# 1-Schematic_IoT_Board.net
KiCad netlist of a schematic drawn in EasyEDA
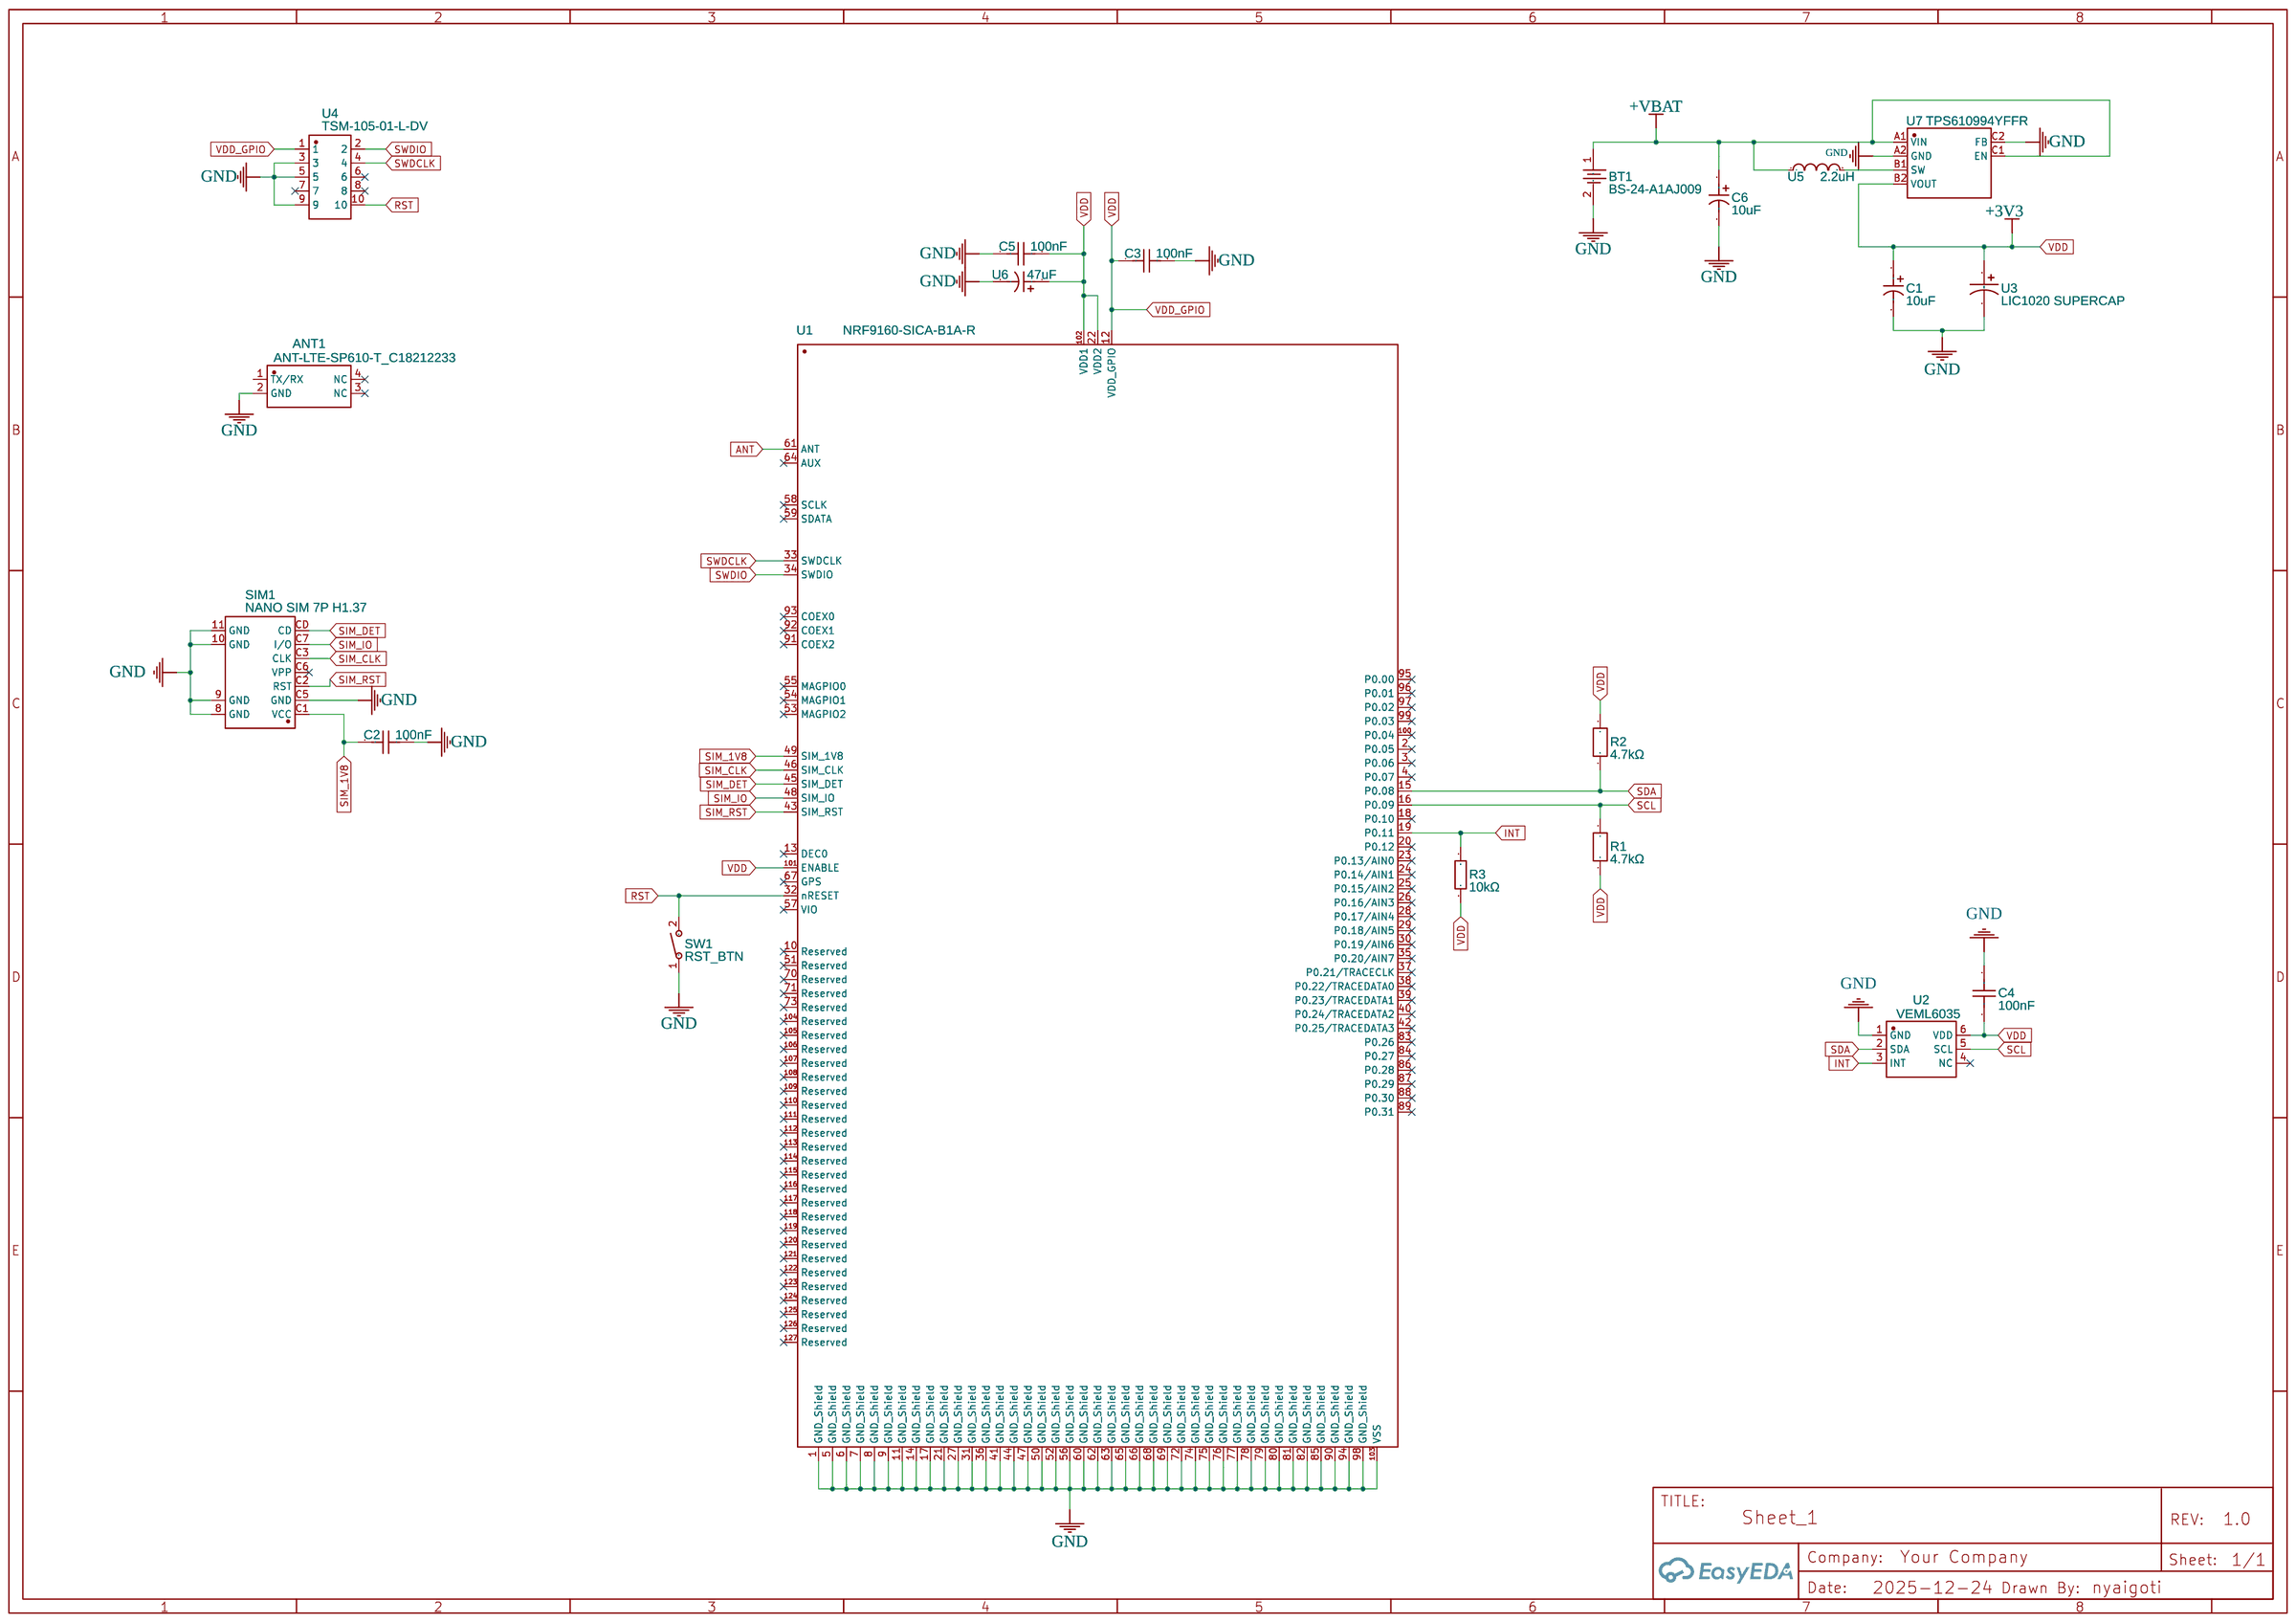
[diagram p0: schematic sheet]

(export (version "E")
  (design (tool "Eeschema 10.0.6"))
  (components
    (comp (ref "ANT1")
      (value "ANT-LTE-SP610-T_C18212233")
      (fields
        (field (name "Manufacturer Part") "ANT-LTE-SP610-T")
        (field (name "Manufacturer") "TE Connectivity(泰科电子)")
      )
      (libsource (lib "") (part "ANT-LTE-SP610-T_C18212233"))
    )
    (comp (ref "BT1")
      (value "BS-24-A1AJ009")
      (fields (field (name "Manufacturer") "MYOUNG(美阳)"))
      (libsource (lib "") (part "BS-24-A1AJ009"))
    )
    (comp (ref "C1")
      (value "10uF")
      (fields
        (field (name "Manufacturer Part") "293D106X9016B2TE3")
        (field (name "Manufacturer") "VISHAY(威世)")
      )
      (libsource (lib "") (part "293D106X9016B2TE3"))
    )
    (comp (ref "C2")
      (value "100nF")
      (fields
        (field (name "Manufacturer Part") "FCC0603B104K500CT")
        (field (name "Manufacturer") "FOJAN(富捷)")
      )
      (libsource (lib "") (part "FCC0603B104K500CT"))
    )
    (comp (ref "C3")
      (value "100nF")
      (fields
        (field (name "Manufacturer Part") "FCC0603B104K500CT")
        (field (name "Manufacturer") "FOJAN(富捷)")
      )
      (libsource (lib "") (part "FCC0603B104K500CT"))
    )
    (comp (ref "C4")
      (value "100nF")
      (fields
        (field (name "Manufacturer Part") "FCC0603B104K500CT")
        (field (name "Manufacturer") "FOJAN(富捷)")
      )
      (libsource (lib "") (part "FCC0603B104K500CT_1"))
    )
    (comp (ref "C5")
      (value "100nF")
      (fields
        (field (name "Manufacturer Part") "FCC0603B104K500CT")
        (field (name "Manufacturer") "FOJAN(富捷)")
      )
      (libsource (lib "") (part "FCC0603B104K500CT"))
    )
    (comp (ref "C6")
      (value "10uF")
      (fields
        (field (name "Manufacturer Part") "293D106X9016B2TE3")
        (field (name "Manufacturer") "VISHAY(威世)")
      )
      (libsource (lib "") (part "293D106X9016B2TE3"))
    )
    (comp (ref "R1")
      (value "4.7kΩ")
      (fields
        (field (name "Manufacturer Part") "CR0603F4K70P05Z")
        (field (name "Manufacturer") "EVER OHMS(天二科技)")
      )
      (libsource (lib "") (part "CR0603F4K70P05Z"))
    )
    (comp (ref "R2")
      (value "4.7kΩ")
      (fields
        (field (name "Manufacturer Part") "CR0603F4K70P05Z")
        (field (name "Manufacturer") "EVER OHMS(天二科技)")
      )
      (libsource (lib "") (part "CR0603F4K70P05Z_1"))
    )
    (comp (ref "R3")
      (value "10kΩ")
      (fields
        (field (name "Manufacturer Part") "TR0603B10K0P0525Z")
        (field (name "Manufacturer") "EVER OHMS(天二科技)")
      )
      (libsource (lib "") (part "TR0603B10KP05250.1W"))
    )
    (comp (ref "SIM1")
      (value "NANO SIM 7P H1.37")
      (fields (field (name "Manufacturer") "SHOU HAN(首韩)"))
      (libsource (lib "") (part "NANO SIM 7P H1.37"))
    )
    (comp (ref "SW1")
      (value "RST_BTN")
      (fields
        (field (name "Manufacturer Part") "HX 3x4x2-2P-1.6N TACTILE SWITCH")
        (field (name "Manufacturer") "hanxia(韩下)")
      )
      (libsource (lib "") (part "HX 3X4X2-2P-1.6N TACTILE SWITCH"))
    )
    (comp (ref "U1")
      (value "NRF9160-SICA-B1A-R")
      (fields (field (name "Manufacturer") "NORDIC"))
      (libsource (lib "") (part "NRF9160-SICA-B1A-R"))
    )
    (comp (ref "U2")
      (value "VEML6035")
      (fields (field (name "Manufacturer") "VISHAY(威世)"))
      (libsource (lib "") (part "VEML6035"))
    )
    (comp (ref "U3")
      (value "LIC1020 SUPERCAP")
      (fields
        (field (name "Manufacturer Part") "LIC1020N3R8C080")
        (field (name "Manufacturer") "KNSCHA(科尼盛)")
      )
      (libsource (lib "") (part "LIC1020N3R8C080"))
    )
    (comp (ref "U4")
      (value "TSM-105-01-L-DV")
      (fields (field (name "Manufacturer") "SAMTEC"))
      (libsource (lib "") (part "TSM-105-01-L-DV"))
    )
    (comp (ref "U5")
      (value "2.2uH")
      (fields (field (name "Manufacturer Part") "APH252010T2R2M") (field (name "Manufacturer") "APV(爱普微)"))
      (libsource (lib "") (part "APH252010T2R2M"))
    )
    (comp (ref "U6")
      (value "47uF")
      (fields
        (field (name "Manufacturer Part") "EMLA500ARA470MF80G")
        (field (name "Manufacturer") "NCC(日本贵弥功)")
      )
      (libsource (lib "") (part "EMLA500ARA470MF80G"))
    )
    (comp (ref "U7")
      (value "TPS610994YFFR")
      (fields (field (name "Manufacturer") "TI(德州仪器)"))
      (libsource (lib "") (part "TPS610994YFFR"))
    )
  )
  (nets
    (net (code "1") (name "+VBAT") (class "Default")
      (node (ref "BT1") (pin "1") (pinfunction "1_1") (pintype "input"))
      (node (ref "C6") (pin "1") (pinfunction "1_1") (pintype "input"))
      (node (ref "U5") (pin "1") (pinfunction "1_1") (pintype "unspecified"))
      (node (ref "U7") (pin "A1") (pinfunction "VIN_A1") (pintype "unspecified"))
      (node (ref "U7") (pin "C1") (pinfunction "EN_C1") (pintype "unspecified"))
    )
    (net (code "2") (name "ANT") (class "Default")
      (node (ref "U1") (pin "61") (pinfunction "ANT_61") (pintype "unspecified"))
    )
    (net (code "3") (name "GND") (class "Default")
      (node (ref "ANT1") (pin "2") (pinfunction "GND_2") (pintype "unspecified"))
      (node (ref "BT1") (pin "2") (pinfunction "2_2") (pintype "input"))
      (node (ref "C1") (pin "2") (pinfunction "2_2") (pintype "input"))
      (node (ref "C2") (pin "2") (pinfunction "2_2") (pintype "unspecified"))
      (node (ref "C3") (pin "2") (pinfunction "2_2") (pintype "unspecified"))
      (node (ref "C4") (pin "1") (pinfunction "1_1") (pintype "unspecified"))
      (node (ref "C5") (pin "1") (pinfunction "1_1") (pintype "unspecified"))
      (node (ref "C6") (pin "2") (pinfunction "2_2") (pintype "input"))
      (node (ref "SIM1") (pin "10") (pinfunction "GND_10") (pintype "unspecified"))
      (node (ref "SIM1") (pin "11") (pinfunction "GND_11") (pintype "unspecified"))
      (node (ref "SIM1") (pin "8") (pinfunction "GND_8") (pintype "unspecified"))
      (node (ref "SIM1") (pin "9") (pinfunction "GND_9") (pintype "unspecified"))
      (node (ref "SIM1") (pin "C5") (pinfunction "GND_C5") (pintype "unspecified"))
      (node (ref "SW1") (pin "1") (pinfunction "1_1") (pintype "unspecified"))
      (node (ref "U1") (pin "1") (pinfunction "GND_Shield_1") (pintype "unspecified"))
      (node (ref "U1") (pin "103") (pinfunction "VSS_103") (pintype "unspecified"))
      (node (ref "U1") (pin "11") (pinfunction "GND_Shield_11") (pintype "unspecified"))
      (node (ref "U1") (pin "14") (pinfunction "GND_Shield_14") (pintype "unspecified"))
      (node (ref "U1") (pin "17") (pinfunction "GND_Shield_17") (pintype "unspecified"))
      (node (ref "U1") (pin "21") (pinfunction "GND_Shield_21") (pintype "unspecified"))
      (node (ref "U1") (pin "27") (pinfunction "GND_Shield_27") (pintype "unspecified"))
      (node (ref "U1") (pin "31") (pinfunction "GND_Shield_31") (pintype "unspecified"))
      (node (ref "U1") (pin "36") (pinfunction "GND_Shield_36") (pintype "unspecified"))
      (node (ref "U1") (pin "41") (pinfunction "GND_Shield_41") (pintype "unspecified"))
      (node (ref "U1") (pin "44") (pinfunction "GND_Shield_44") (pintype "unspecified"))
      (node (ref "U1") (pin "47") (pinfunction "GND_Shield_47") (pintype "unspecified"))
      (node (ref "U1") (pin "5") (pinfunction "GND_Shield_5") (pintype "unspecified"))
      (node (ref "U1") (pin "50") (pinfunction "GND_Shield_50") (pintype "unspecified"))
      (node (ref "U1") (pin "52") (pinfunction "GND_Shield_52") (pintype "unspecified"))
      (node (ref "U1") (pin "56") (pinfunction "GND_Shield_56") (pintype "unspecified"))
      (node (ref "U1") (pin "6") (pinfunction "GND_Shield_6") (pintype "unspecified"))
      (node (ref "U1") (pin "60") (pinfunction "GND_Shield_60") (pintype "unspecified"))
      (node (ref "U1") (pin "62") (pinfunction "GND_Shield_62") (pintype "unspecified"))
      (node (ref "U1") (pin "63") (pinfunction "GND_Shield_63") (pintype "unspecified"))
      (node (ref "U1") (pin "65") (pinfunction "GND_Shield_65") (pintype "unspecified"))
      (node (ref "U1") (pin "66") (pinfunction "GND_Shield_66") (pintype "unspecified"))
      (node (ref "U1") (pin "68") (pinfunction "GND_Shield_68") (pintype "unspecified"))
      (node (ref "U1") (pin "69") (pinfunction "GND_Shield_69") (pintype "unspecified"))
      (node (ref "U1") (pin "7") (pinfunction "GND_Shield_7") (pintype "unspecified"))
      (node (ref "U1") (pin "72") (pinfunction "GND_Shield_72") (pintype "unspecified"))
      (node (ref "U1") (pin "74") (pinfunction "GND_Shield_74") (pintype "unspecified"))
      (node (ref "U1") (pin "75") (pinfunction "GND_Shield_75") (pintype "unspecified"))
      (node (ref "U1") (pin "76") (pinfunction "GND_Shield_76") (pintype "unspecified"))
      (node (ref "U1") (pin "77") (pinfunction "GND_Shield_77") (pintype "unspecified"))
      (node (ref "U1") (pin "78") (pinfunction "GND_Shield_78") (pintype "unspecified"))
      (node (ref "U1") (pin "79") (pinfunction "GND_Shield_79") (pintype "unspecified"))
      (node (ref "U1") (pin "8") (pinfunction "GND_Shield_8") (pintype "unspecified"))
      (node (ref "U1") (pin "80") (pinfunction "GND_Shield_80") (pintype "unspecified"))
      (node (ref "U1") (pin "81") (pinfunction "GND_Shield_81") (pintype "unspecified"))
      (node (ref "U1") (pin "82") (pinfunction "GND_Shield_82") (pintype "unspecified"))
      (node (ref "U1") (pin "85") (pinfunction "GND_Shield_85") (pintype "unspecified"))
      (node (ref "U1") (pin "9") (pinfunction "GND_Shield_9") (pintype "unspecified"))
      (node (ref "U1") (pin "90") (pinfunction "GND_Shield_90") (pintype "unspecified"))
      (node (ref "U1") (pin "94") (pinfunction "GND_Shield_94") (pintype "unspecified"))
      (node (ref "U1") (pin "98") (pinfunction "GND_Shield_98") (pintype "unspecified"))
      (node (ref "U2") (pin "1") (pinfunction "GND_1") (pintype "unspecified"))
      (node (ref "U3") (pin "2") (pinfunction "2_2") (pintype "unspecified"))
      (node (ref "U4") (pin "3") (pinfunction "3_3") (pintype "unspecified"))
      (node (ref "U4") (pin "5") (pinfunction "5_5") (pintype "unspecified"))
      (node (ref "U4") (pin "9") (pinfunction "9_9") (pintype "unspecified"))
      (node (ref "U6") (pin "2") (pinfunction "2_2") (pintype "input"))
      (node (ref "U7") (pin "A2") (pinfunction "GND_A2") (pintype "unspecified"))
      (node (ref "U7") (pin "C2") (pinfunction "FB_C2") (pintype "unspecified"))
    )
    (net (code "4") (name "INT") (class "Default")
      (node (ref "R3") (pin "2") (pinfunction "2_2") (pintype "unspecified"))
      (node (ref "U1") (pin "19") (pinfunction "P0.11_19") (pintype "unspecified"))
      (node (ref "U2") (pin "3") (pinfunction "INT_3") (pintype "unspecified"))
    )
    (net (code "5") (name "Net-(U7-SW)") (class "Default")
      (node (ref "U5") (pin "2") (pinfunction "2_2") (pintype "unspecified"))
      (node (ref "U7") (pin "B1") (pinfunction "SW_B1") (pintype "unspecified"))
    )
    (net (code "6") (name "RST") (class "Default")
      (node (ref "SW1") (pin "2") (pinfunction "2_2") (pintype "unspecified"))
      (node (ref "U1") (pin "32") (pinfunction "nRESET_32") (pintype "unspecified"))
      (node (ref "U4") (pin "10") (pinfunction "10_10") (pintype "unspecified"))
    )
    (net (code "7") (name "SCL") (class "Default")
      (node (ref "R1") (pin "2") (pinfunction "2_2") (pintype "unspecified"))
      (node (ref "U1") (pin "16") (pinfunction "P0.09_16") (pintype "unspecified"))
      (node (ref "U2") (pin "5") (pinfunction "SCL_5") (pintype "unspecified"))
    )
    (net (code "8") (name "SDA") (class "Default")
      (node (ref "R2") (pin "2") (pinfunction "2_2") (pintype "unspecified"))
      (node (ref "U1") (pin "15") (pinfunction "P0.08_15") (pintype "unspecified"))
      (node (ref "U2") (pin "2") (pinfunction "SDA_2") (pintype "unspecified"))
    )
    (net (code "9") (name "SIM_1V8") (class "Default")
      (node (ref "C2") (pin "1") (pinfunction "1_1") (pintype "unspecified"))
      (node (ref "SIM1") (pin "C1") (pinfunction "VCC_C1") (pintype "unspecified"))
      (node (ref "U1") (pin "49") (pinfunction "SIM_1V8_49") (pintype "unspecified"))
    )
    (net (code "10") (name "SIM_CLK") (class "Default")
      (node (ref "SIM1") (pin "C3") (pinfunction "CLK_C3") (pintype "unspecified"))
      (node (ref "U1") (pin "46") (pinfunction "SIM_CLK_46") (pintype "unspecified"))
    )
    (net (code "11") (name "SIM_DET") (class "Default")
      (node (ref "SIM1") (pin "CD") (pinfunction "CD_CD") (pintype "unspecified"))
      (node (ref "U1") (pin "45") (pinfunction "SIM_DET_45") (pintype "unspecified"))
    )
    (net (code "12") (name "SIM_IO") (class "Default")
      (node (ref "SIM1") (pin "C7") (pinfunction "I/O_C7") (pintype "unspecified"))
      (node (ref "U1") (pin "48") (pinfunction "SIM_IO_48") (pintype "unspecified"))
    )
    (net (code "13") (name "SIM_RST") (class "Default")
      (node (ref "SIM1") (pin "C2") (pinfunction "RST_C2") (pintype "unspecified"))
      (node (ref "U1") (pin "43") (pinfunction "SIM_RST_43") (pintype "unspecified"))
    )
    (net (code "14") (name "SWDCLK") (class "Default")
      (node (ref "U1") (pin "33") (pinfunction "SWDCLK_33") (pintype "unspecified"))
      (node (ref "U4") (pin "4") (pinfunction "4_4") (pintype "unspecified"))
    )
    (net (code "15") (name "SWDIO") (class "Default")
      (node (ref "U1") (pin "34") (pinfunction "SWDIO_34") (pintype "unspecified"))
      (node (ref "U4") (pin "2") (pinfunction "2_2") (pintype "unspecified"))
    )
    (net (code "16") (name "VDD") (class "Default")
      (node (ref "C1") (pin "1") (pinfunction "1_1") (pintype "input"))
      (node (ref "C3") (pin "1") (pinfunction "1_1") (pintype "unspecified"))
      (node (ref "C4") (pin "2") (pinfunction "2_2") (pintype "unspecified"))
      (node (ref "C5") (pin "2") (pinfunction "2_2") (pintype "unspecified"))
      (node (ref "R1") (pin "1") (pinfunction "1_1") (pintype "unspecified"))
      (node (ref "R2") (pin "1") (pinfunction "1_1") (pintype "unspecified"))
      (node (ref "R3") (pin "1") (pinfunction "1_1") (pintype "unspecified"))
      (node (ref "U1") (pin "101") (pinfunction "ENABLE_101") (pintype "unspecified"))
      (node (ref "U1") (pin "102") (pinfunction "VDD1_102") (pintype "unspecified"))
      (node (ref "U1") (pin "12") (pinfunction "VDD_GPIO_12") (pintype "unspecified"))
      (node (ref "U1") (pin "22") (pinfunction "VDD2_22") (pintype "unspecified"))
      (node (ref "U2") (pin "6") (pinfunction "VDD_6") (pintype "unspecified"))
      (node (ref "U3") (pin "1") (pinfunction "1_1") (pintype "unspecified"))
      (node (ref "U4") (pin "1") (pinfunction "1_1") (pintype "unspecified"))
      (node (ref "U6") (pin "1") (pinfunction "1_1") (pintype "input"))
      (node (ref "U7") (pin "B2") (pinfunction "VOUT_B2") (pintype "unspecified"))
    )
    (net (code "17") (name "unconnected-(ANT1-NC-Pad3)") (class "Default")
      (node (ref "ANT1") (pin "3") (pinfunction "NC_3") (pintype "unspecified+no_connect"))
    )
    (net (code "18") (name "unconnected-(ANT1-NC-Pad4)") (class "Default")
      (node (ref "ANT1") (pin "4") (pinfunction "NC_4") (pintype "unspecified+no_connect"))
    )
    (net (code "19") (name "unconnected-(ANT1-TX{slash}RX-Pad1)") (class "Default")
      (node (ref "ANT1") (pin "1") (pinfunction "TX/RX_1") (pintype "unspecified"))
    )
    (net (code "20") (name "unconnected-(SIM1-VPP-PadC6)") (class "Default")
      (node (ref "SIM1") (pin "C6") (pinfunction "VPP_C6") (pintype "unspecified+no_connect"))
    )
    (net (code "21") (name "unconnected-(U1-AUX-Pad64)") (class "Default")
      (node (ref "U1") (pin "64") (pinfunction "AUX_64") (pintype "unspecified+no_connect"))
    )
    (net (code "22") (name "unconnected-(U1-COEX0-Pad93)") (class "Default")
      (node (ref "U1") (pin "93") (pinfunction "COEX0_93") (pintype "unspecified+no_connect"))
    )
    (net (code "23") (name "unconnected-(U1-COEX1-Pad92)") (class "Default")
      (node (ref "U1") (pin "92") (pinfunction "COEX1_92") (pintype "unspecified+no_connect"))
    )
    (net (code "24") (name "unconnected-(U1-COEX2-Pad91)") (class "Default")
      (node (ref "U1") (pin "91") (pinfunction "COEX2_91") (pintype "unspecified+no_connect"))
    )
    (net (code "25") (name "unconnected-(U1-DEC0-Pad13)") (class "Default")
      (node (ref "U1") (pin "13") (pinfunction "DEC0_13") (pintype "unspecified+no_connect"))
    )
    (net (code "26") (name "unconnected-(U1-GPS-Pad67)") (class "Default")
      (node (ref "U1") (pin "67") (pinfunction "GPS_67") (pintype "unspecified+no_connect"))
    )
    (net (code "27") (name "unconnected-(U1-MAGPIO0-Pad55)") (class "Default")
      (node (ref "U1") (pin "55") (pinfunction "MAGPIO0_55") (pintype "unspecified+no_connect"))
    )
    (net (code "28") (name "unconnected-(U1-MAGPIO1-Pad54)") (class "Default")
      (node (ref "U1") (pin "54") (pinfunction "MAGPIO1_54") (pintype "unspecified+no_connect"))
    )
    (net (code "29") (name "unconnected-(U1-MAGPIO2-Pad53)") (class "Default")
      (node (ref "U1") (pin "53") (pinfunction "MAGPIO2_53") (pintype "unspecified+no_connect"))
    )
    (net (code "30") (name "unconnected-(U1-P0.00-Pad95)") (class "Default")
      (node (ref "U1") (pin "95") (pinfunction "P0.00_95") (pintype "unspecified+no_connect"))
    )
    (net (code "31") (name "unconnected-(U1-P0.01-Pad96)") (class "Default")
      (node (ref "U1") (pin "96") (pinfunction "P0.01_96") (pintype "unspecified+no_connect"))
    )
    (net (code "32") (name "unconnected-(U1-P0.02-Pad97)") (class "Default")
      (node (ref "U1") (pin "97") (pinfunction "P0.02_97") (pintype "unspecified+no_connect"))
    )
    (net (code "33") (name "unconnected-(U1-P0.03-Pad99)") (class "Default")
      (node (ref "U1") (pin "99") (pinfunction "P0.03_99") (pintype "unspecified+no_connect"))
    )
    (net (code "34") (name "unconnected-(U1-P0.04-Pad100)") (class "Default")
      (node (ref "U1") (pin "100") (pinfunction "P0.04_100") (pintype "unspecified+no_connect"))
    )
    (net (code "35") (name "unconnected-(U1-P0.05-Pad2)") (class "Default")
      (node (ref "U1") (pin "2") (pinfunction "P0.05_2") (pintype "unspecified+no_connect"))
    )
    (net (code "36") (name "unconnected-(U1-P0.06-Pad3)") (class "Default")
      (node (ref "U1") (pin "3") (pinfunction "P0.06_3") (pintype "unspecified+no_connect"))
    )
    (net (code "37") (name "unconnected-(U1-P0.07-Pad4)") (class "Default")
      (node (ref "U1") (pin "4") (pinfunction "P0.07_4") (pintype "unspecified+no_connect"))
    )
    (net (code "38") (name "unconnected-(U1-P0.10-Pad18)") (class "Default")
      (node (ref "U1") (pin "18") (pinfunction "P0.10_18") (pintype "unspecified+no_connect"))
    )
    (net (code "39") (name "unconnected-(U1-P0.12-Pad20)") (class "Default")
      (node (ref "U1") (pin "20") (pinfunction "P0.12_20") (pintype "unspecified+no_connect"))
    )
    (net (code "40") (name "unconnected-(U1-P0.13{slash}AIN0-Pad23)") (class "Default")
      (node (ref "U1") (pin "23") (pinfunction "P0.13/AIN0_23") (pintype "unspecified+no_connect"))
    )
    (net (code "41") (name "unconnected-(U1-P0.14{slash}AIN1-Pad24)") (class "Default")
      (node (ref "U1") (pin "24") (pinfunction "P0.14/AIN1_24") (pintype "unspecified+no_connect"))
    )
    (net (code "42") (name "unconnected-(U1-P0.15{slash}AIN2-Pad25)") (class "Default")
      (node (ref "U1") (pin "25") (pinfunction "P0.15/AIN2_25") (pintype "unspecified+no_connect"))
    )
    (net (code "43") (name "unconnected-(U1-P0.16{slash}AIN3-Pad26)") (class "Default")
      (node (ref "U1") (pin "26") (pinfunction "P0.16/AIN3_26") (pintype "unspecified+no_connect"))
    )
    (net (code "44") (name "unconnected-(U1-P0.17{slash}AIN4-Pad28)") (class "Default")
      (node (ref "U1") (pin "28") (pinfunction "P0.17/AIN4_28") (pintype "unspecified+no_connect"))
    )
    (net (code "45") (name "unconnected-(U1-P0.18{slash}AIN5-Pad29)") (class "Default")
      (node (ref "U1") (pin "29") (pinfunction "P0.18/AIN5_29") (pintype "unspecified+no_connect"))
    )
    (net (code "46") (name "unconnected-(U1-P0.19{slash}AIN6-Pad30)") (class "Default")
      (node (ref "U1") (pin "30") (pinfunction "P0.19/AIN6_30") (pintype "unspecified+no_connect"))
    )
    (net (code "47") (name "unconnected-(U1-P0.20{slash}AIN7-Pad35)") (class "Default")
      (node (ref "U1") (pin "35") (pinfunction "P0.20/AIN7_35") (pintype "unspecified+no_connect"))
    )
    (net (code "48") (name "unconnected-(U1-P0.21{slash}TRACECLK-Pad37)") (class "Default")
      (node (ref "U1") (pin "37") (pinfunction "P0.21/TRACECLK_37") (pintype "unspecified+no_connect"))
    )
    (net (code "49") (name "unconnected-(U1-P0.22{slash}TRACEDATA0-Pad38)") (class "Default")
      (node (ref "U1") (pin "38") (pinfunction "P0.22/TRACEDATA0_38") (pintype "unspecified+no_connect"))
    )
    (net (code "50") (name "unconnected-(U1-P0.23{slash}TRACEDATA1-Pad39)") (class "Default")
      (node (ref "U1") (pin "39") (pinfunction "P0.23/TRACEDATA1_39") (pintype "unspecified+no_connect"))
    )
    (net (code "51") (name "unconnected-(U1-P0.24{slash}TRACEDATA2-Pad40)") (class "Default")
      (node (ref "U1") (pin "40") (pinfunction "P0.24/TRACEDATA2_40") (pintype "unspecified+no_connect"))
    )
    (net (code "52") (name "unconnected-(U1-P0.25{slash}TRACEDATA3-Pad42)") (class "Default")
      (node (ref "U1") (pin "42") (pinfunction "P0.25/TRACEDATA3_42") (pintype "unspecified+no_connect"))
    )
    (net (code "53") (name "unconnected-(U1-P0.26-Pad83)") (class "Default")
      (node (ref "U1") (pin "83") (pinfunction "P0.26_83") (pintype "unspecified+no_connect"))
    )
    (net (code "54") (name "unconnected-(U1-P0.27-Pad84)") (class "Default")
      (node (ref "U1") (pin "84") (pinfunction "P0.27_84") (pintype "unspecified+no_connect"))
    )
    (net (code "55") (name "unconnected-(U1-P0.28-Pad86)") (class "Default")
      (node (ref "U1") (pin "86") (pinfunction "P0.28_86") (pintype "unspecified+no_connect"))
    )
    (net (code "56") (name "unconnected-(U1-P0.29-Pad87)") (class "Default")
      (node (ref "U1") (pin "87") (pinfunction "P0.29_87") (pintype "unspecified+no_connect"))
    )
    (net (code "57") (name "unconnected-(U1-P0.30-Pad88)") (class "Default")
      (node (ref "U1") (pin "88") (pinfunction "P0.30_88") (pintype "unspecified+no_connect"))
    )
    (net (code "58") (name "unconnected-(U1-P0.31-Pad89)") (class "Default")
      (node (ref "U1") (pin "89") (pinfunction "P0.31_89") (pintype "unspecified+no_connect"))
    )
    (net (code "59") (name "unconnected-(U1-Reserved-Pad10)") (class "Default")
      (node (ref "U1") (pin "10") (pinfunction "Reserved_10") (pintype "unspecified+no_connect"))
    )
    (net (code "60") (name "unconnected-(U1-Reserved-Pad51)") (class "Default")
      (node (ref "U1") (pin "51") (pinfunction "Reserved_51") (pintype "unspecified+no_connect"))
    )
    (net (code "61") (name "unconnected-(U1-Reserved-Pad70)") (class "Default")
      (node (ref "U1") (pin "70") (pinfunction "Reserved_70") (pintype "unspecified+no_connect"))
    )
    (net (code "62") (name "unconnected-(U1-Reserved-Pad71)") (class "Default")
      (node (ref "U1") (pin "71") (pinfunction "Reserved_71") (pintype "unspecified+no_connect"))
    )
    (net (code "63") (name "unconnected-(U1-Reserved-Pad73)") (class "Default")
      (node (ref "U1") (pin "73") (pinfunction "Reserved_73") (pintype "unspecified+no_connect"))
    )
    (net (code "64") (name "unconnected-(U1-Reserved-Pad104)") (class "Default")
      (node (ref "U1") (pin "104") (pinfunction "Reserved_104") (pintype "unspecified+no_connect"))
    )
    (net (code "65") (name "unconnected-(U1-Reserved-Pad105)") (class "Default")
      (node (ref "U1") (pin "105") (pinfunction "Reserved_105") (pintype "unspecified+no_connect"))
    )
    (net (code "66") (name "unconnected-(U1-Reserved-Pad106)") (class "Default")
      (node (ref "U1") (pin "106") (pinfunction "Reserved_106") (pintype "unspecified+no_connect"))
    )
    (net (code "67") (name "unconnected-(U1-Reserved-Pad107)") (class "Default")
      (node (ref "U1") (pin "107") (pinfunction "Reserved_107") (pintype "unspecified+no_connect"))
    )
    (net (code "68") (name "unconnected-(U1-Reserved-Pad108)") (class "Default")
      (node (ref "U1") (pin "108") (pinfunction "Reserved_108") (pintype "unspecified+no_connect"))
    )
    (net (code "69") (name "unconnected-(U1-Reserved-Pad109)") (class "Default")
      (node (ref "U1") (pin "109") (pinfunction "Reserved_109") (pintype "unspecified+no_connect"))
    )
    (net (code "70") (name "unconnected-(U1-Reserved-Pad110)") (class "Default")
      (node (ref "U1") (pin "110") (pinfunction "Reserved_110") (pintype "unspecified+no_connect"))
    )
    (net (code "71") (name "unconnected-(U1-Reserved-Pad111)") (class "Default")
      (node (ref "U1") (pin "111") (pinfunction "Reserved_111") (pintype "unspecified+no_connect"))
    )
    (net (code "72") (name "unconnected-(U1-Reserved-Pad112)") (class "Default")
      (node (ref "U1") (pin "112") (pinfunction "Reserved_112") (pintype "unspecified+no_connect"))
    )
    (net (code "73") (name "unconnected-(U1-Reserved-Pad113)") (class "Default")
      (node (ref "U1") (pin "113") (pinfunction "Reserved_113") (pintype "unspecified+no_connect"))
    )
    (net (code "74") (name "unconnected-(U1-Reserved-Pad114)") (class "Default")
      (node (ref "U1") (pin "114") (pinfunction "Reserved_114") (pintype "unspecified+no_connect"))
    )
    (net (code "75") (name "unconnected-(U1-Reserved-Pad115)") (class "Default")
      (node (ref "U1") (pin "115") (pinfunction "Reserved_115") (pintype "unspecified+no_connect"))
    )
    (net (code "76") (name "unconnected-(U1-Reserved-Pad116)") (class "Default")
      (node (ref "U1") (pin "116") (pinfunction "Reserved_116") (pintype "unspecified+no_connect"))
    )
    (net (code "77") (name "unconnected-(U1-Reserved-Pad117)") (class "Default")
      (node (ref "U1") (pin "117") (pinfunction "Reserved_117") (pintype "unspecified+no_connect"))
    )
    (net (code "78") (name "unconnected-(U1-Reserved-Pad118)") (class "Default")
      (node (ref "U1") (pin "118") (pinfunction "Reserved_118") (pintype "unspecified+no_connect"))
    )
    (net (code "79") (name "unconnected-(U1-Reserved-Pad119)") (class "Default")
      (node (ref "U1") (pin "119") (pinfunction "Reserved_119") (pintype "unspecified+no_connect"))
    )
    (net (code "80") (name "unconnected-(U1-Reserved-Pad120)") (class "Default")
      (node (ref "U1") (pin "120") (pinfunction "Reserved_120") (pintype "unspecified+no_connect"))
    )
    (net (code "81") (name "unconnected-(U1-Reserved-Pad121)") (class "Default")
      (node (ref "U1") (pin "121") (pinfunction "Reserved_121") (pintype "unspecified+no_connect"))
    )
    (net (code "82") (name "unconnected-(U1-Reserved-Pad122)") (class "Default")
      (node (ref "U1") (pin "122") (pinfunction "Reserved_122") (pintype "unspecified+no_connect"))
    )
    (net (code "83") (name "unconnected-(U1-Reserved-Pad123)") (class "Default")
      (node (ref "U1") (pin "123") (pinfunction "Reserved_123") (pintype "unspecified+no_connect"))
    )
    (net (code "84") (name "unconnected-(U1-Reserved-Pad124)") (class "Default")
      (node (ref "U1") (pin "124") (pinfunction "Reserved_124") (pintype "unspecified+no_connect"))
    )
    (net (code "85") (name "unconnected-(U1-Reserved-Pad125)") (class "Default")
      (node (ref "U1") (pin "125") (pinfunction "Reserved_125") (pintype "unspecified+no_connect"))
    )
    (net (code "86") (name "unconnected-(U1-Reserved-Pad126)") (class "Default")
      (node (ref "U1") (pin "126") (pinfunction "Reserved_126") (pintype "unspecified+no_connect"))
    )
    (net (code "87") (name "unconnected-(U1-Reserved-Pad127)") (class "Default")
      (node (ref "U1") (pin "127") (pinfunction "Reserved_127") (pintype "unspecified+no_connect"))
    )
    (net (code "88") (name "unconnected-(U1-SCLK-Pad58)") (class "Default")
      (node (ref "U1") (pin "58") (pinfunction "SCLK_58") (pintype "unspecified+no_connect"))
    )
    (net (code "89") (name "unconnected-(U1-SDATA-Pad59)") (class "Default")
      (node (ref "U1") (pin "59") (pinfunction "SDATA_59") (pintype "unspecified+no_connect"))
    )
    (net (code "90") (name "unconnected-(U1-VIO-Pad57)") (class "Default")
      (node (ref "U1") (pin "57") (pinfunction "VIO_57") (pintype "unspecified+no_connect"))
    )
    (net (code "91") (name "unconnected-(U2-NC-Pad4)") (class "Default")
      (node (ref "U2") (pin "4") (pinfunction "NC_4") (pintype "unspecified+no_connect"))
    )
    (net (code "92") (name "unconnected-(U4-Pad6)") (class "Default")
      (node (ref "U4") (pin "6") (pinfunction "6_6") (pintype "unspecified+no_connect"))
    )
    (net (code "93") (name "unconnected-(U4-Pad7)") (class "Default")
      (node (ref "U4") (pin "7") (pinfunction "7_7") (pintype "unspecified+no_connect"))
    )
    (net (code "94") (name "unconnected-(U4-Pad8)") (class "Default")
      (node (ref "U4") (pin "8") (pinfunction "8_8") (pintype "unspecified+no_connect"))
    )
  )
)
